# Science.net
KiCad netlist of a schematic drawn in Altium Designer
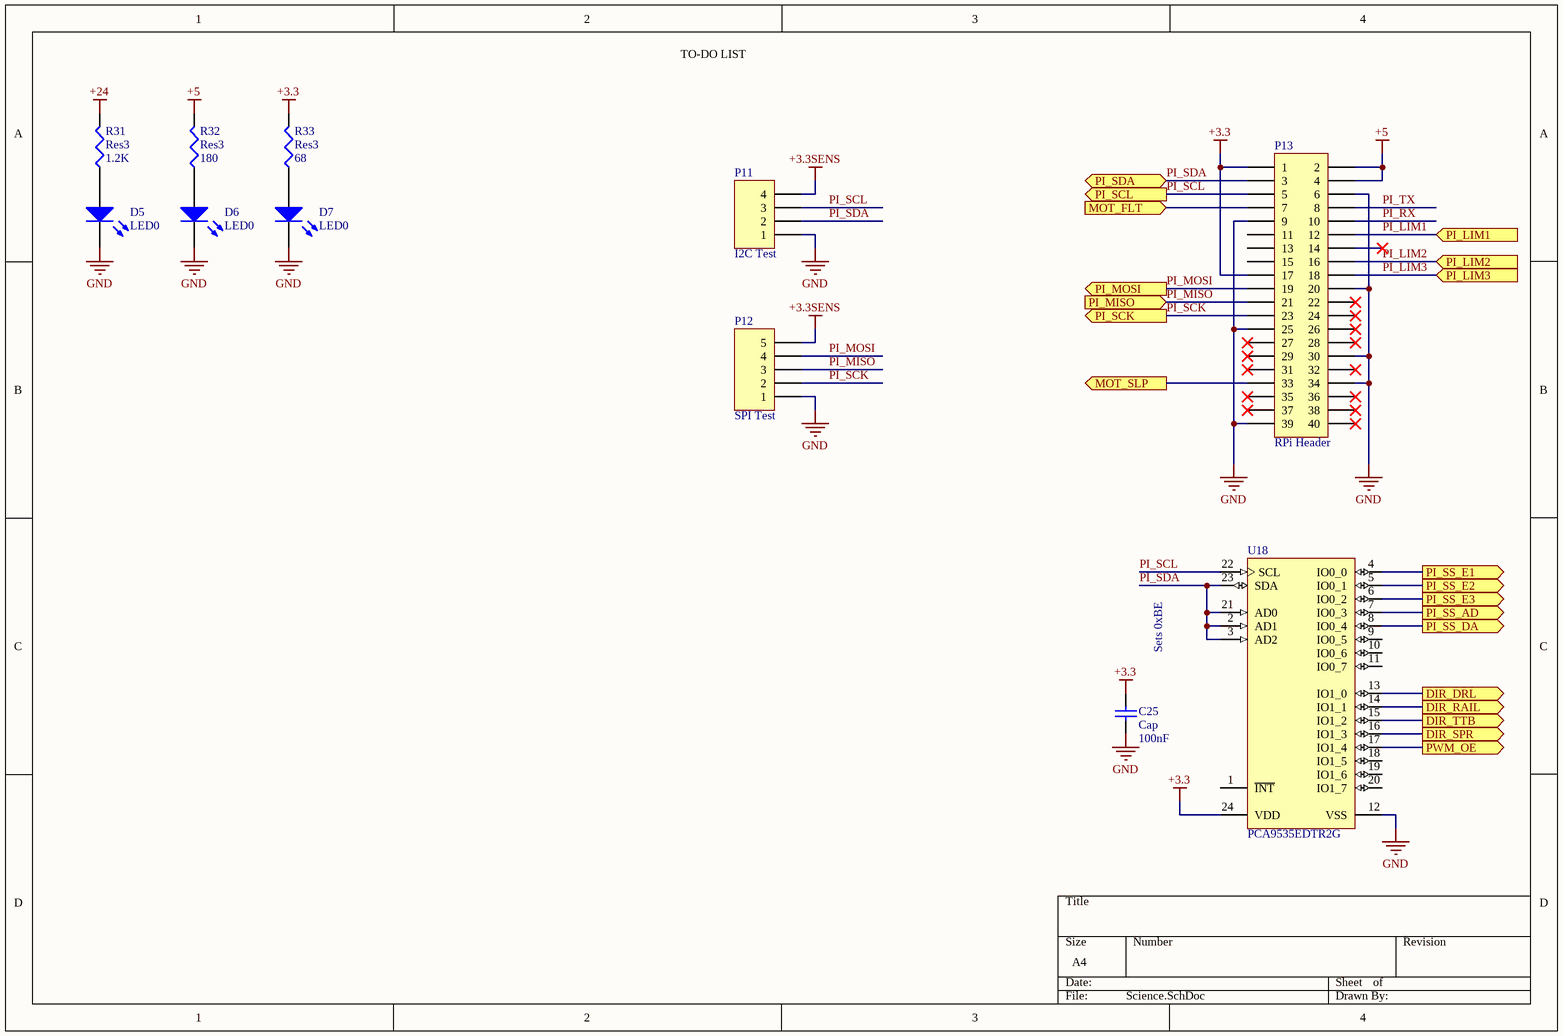
[diagram p0: Science.SchDoc]

(export (version "E")
  (design (tool "Eeschema 10.0.6"))
  (components
    (comp (ref "C25")
      (value "Cap")
      (footprint "C0805")
      (description "Capacitor")
      (fields (field (name "ALTIUM_VALUE") "100nF") (field (name "PUBLISHER") "Altium Limited"))
      (libsource (lib "Miscellaneous Devices") (part "Cap"))
    )
    (comp (ref "D5")
      (value "LED0")
      (footprint "1608[0603]")
      (description "Typical INFRARED GaAs LED")
      (fields (field (name "PUBLISHER") "Altium Limited"))
      (libsource (lib "Miscellaneous Devices") (part "LED0"))
    )
    (comp (ref "D6")
      (value "LED0")
      (footprint "1608[0603]")
      (description "Typical INFRARED GaAs LED")
      (fields (field (name "PUBLISHER") "Altium Limited"))
      (libsource (lib "Miscellaneous Devices") (part "LED0"))
    )
    (comp (ref "D7")
      (value "LED0")
      (footprint "1608[0603]")
      (description "Typical INFRARED GaAs LED")
      (fields (field (name "PUBLISHER") "Altium Limited"))
      (libsource (lib "Miscellaneous Devices") (part "LED0"))
    )
    (comp (ref "P11")
      (value "I2C Test")
      (footprint "HDR1X4")
      (description "Header, 4-Pin")
      (fields (field (name "PUBLISHER") "Altium Limited"))
      (libsource (lib "Miscellaneous Connectors") (part "Header 4"))
    )
    (comp (ref "P12")
      (value "SPI Test")
      (footprint "HDR1X5")
      (description "Header, 5-Pin")
      (fields (field (name "PUBLISHER") "Altium Limited"))
      (libsource (lib "Miscellaneous Connectors") (part "Header 5"))
    )
    (comp (ref "P13")
      (value "RPi Header")
      (footprint "RPi-3B+")
      (description "Header, 20-Pin, Dual row")
      (fields (field (name "PUBLISHER") "Altium Limited"))
      (libsource (lib "Miscellaneous Connectors") (part "Header 20X2"))
    )
    (comp (ref "R31")
      (value "Res3")
      (footprint "C0805")
      (description "Resistor")
      (fields (field (name "ALTIUM_VALUE") "1.2K") (field (name "PUBLISHER") "Altium Limited"))
      (libsource (lib "Miscellaneous Devices") (part "Res3"))
    )
    (comp (ref "R32")
      (value "Res3")
      (footprint "C0805")
      (description "Resistor")
      (fields (field (name "ALTIUM_VALUE") "180") (field (name "PUBLISHER") "Altium Limited"))
      (libsource (lib "Miscellaneous Devices") (part "Res3"))
    )
    (comp (ref "R33")
      (value "Res3")
      (footprint "C0805")
      (description "Resistor")
      (fields (field (name "ALTIUM_VALUE") "68") (field (name "PUBLISHER") "Altium Limited"))
      (libsource (lib "Miscellaneous Devices") (part "Res3"))
    )
    (comp (ref "U18")
      (value "PCA9535EDTR2G")
      (footprint "ONSC-TSSOP-24-948H_V")
      (fields (field (name "MANUFACTURER") "On Semiconductor"))
      (libsource (lib "Altium Content Vault") (part "ONSC-PCA9535E-24"))
    )
  )
  (nets
    (net (code "1") (name "+3.3") (class "Default")
      (node (ref "C25") (pin "2") (pinfunction "2_2") (pintype "passive"))
      (node (ref "P13") (pin "1") (pinfunction "1_1") (pintype "passive"))
      (node (ref "P13") (pin "17") (pinfunction "17_17") (pintype "passive"))
      (node (ref "R33") (pin "2") (pinfunction "2_2") (pintype "passive"))
      (node (ref "U18") (pin "24") (pinfunction "VDD_24") (pintype "power_in"))
    )
    (net (code "2") (name "+3.3SENS") (class "Default")
      (node (ref "P11") (pin "4") (pinfunction "4_4") (pintype "passive"))
      (node (ref "P12") (pin "5") (pinfunction "5_5") (pintype "passive"))
    )
    (net (code "3") (name "+5") (class "Default")
      (node (ref "P13") (pin "2") (pinfunction "2_2") (pintype "passive"))
      (node (ref "P13") (pin "4") (pinfunction "4_4") (pintype "passive"))
      (node (ref "R32") (pin "2") (pinfunction "2_2") (pintype "passive"))
    )
    (net (code "4") (name "+24") (class "Default")
      (node (ref "R31") (pin "2") (pinfunction "2_2") (pintype "passive"))
    )
    (net (code "5") (name "/DIR_DRL") (class "Default")
      (node (ref "U18") (pin "13") (pinfunction "IO1_0_13") (pintype "bidirectional"))
    )
    (net (code "6") (name "/DIR_RAIL") (class "Default")
      (node (ref "U18") (pin "14") (pinfunction "IO1_1_14") (pintype "bidirectional"))
    )
    (net (code "7") (name "/DIR_SPR") (class "Default")
      (node (ref "U18") (pin "16") (pinfunction "IO1_3_16") (pintype "bidirectional"))
    )
    (net (code "8") (name "/DIR_TTB") (class "Default")
      (node (ref "U18") (pin "15") (pinfunction "IO1_2_15") (pintype "bidirectional"))
    )
    (net (code "9") (name "/MOT_FLT") (class "Default")
      (node (ref "P13") (pin "7") (pinfunction "7_7") (pintype "passive"))
    )
    (net (code "10") (name "/MOT_SLP") (class "Default")
      (node (ref "P13") (pin "33") (pinfunction "33_33") (pintype "passive"))
    )
    (net (code "11") (name "/PI_LIM1") (class "Default")
      (node (ref "P13") (pin "12") (pinfunction "12_12") (pintype "passive"))
    )
    (net (code "12") (name "/PI_LIM2") (class "Default")
      (node (ref "P13") (pin "16") (pinfunction "16_16") (pintype "passive"))
    )
    (net (code "13") (name "/PI_LIM3") (class "Default")
      (node (ref "P13") (pin "18") (pinfunction "18_18") (pintype "passive"))
    )
    (net (code "14") (name "/PI_MISO") (class "Default")
      (node (ref "P12") (pin "3") (pinfunction "3_3") (pintype "passive"))
      (node (ref "P13") (pin "21") (pinfunction "21_21") (pintype "passive"))
    )
    (net (code "15") (name "/PI_MOSI") (class "Default")
      (node (ref "P12") (pin "4") (pinfunction "4_4") (pintype "passive"))
      (node (ref "P13") (pin "19") (pinfunction "19_19") (pintype "passive"))
    )
    (net (code "16") (name "/PI_RX") (class "Default")
      (node (ref "P13") (pin "10") (pinfunction "10_10") (pintype "passive"))
    )
    (net (code "17") (name "/PI_SCK") (class "Default")
      (node (ref "P12") (pin "2") (pinfunction "2_2") (pintype "passive"))
      (node (ref "P13") (pin "23") (pinfunction "23_23") (pintype "passive"))
    )
    (net (code "18") (name "/PI_SCL") (class "Default")
      (node (ref "P11") (pin "3") (pinfunction "3_3") (pintype "passive"))
      (node (ref "P13") (pin "5") (pinfunction "5_5") (pintype "passive"))
      (node (ref "U18") (pin "22") (pinfunction "SCL_22") (pintype "input"))
    )
    (net (code "19") (name "/PI_SDA") (class "Default")
      (node (ref "P11") (pin "2") (pinfunction "2_2") (pintype "passive"))
      (node (ref "P13") (pin "3") (pinfunction "3_3") (pintype "passive"))
      (node (ref "U18") (pin "2") (pinfunction "AD1_2") (pintype "input"))
      (node (ref "U18") (pin "21") (pinfunction "AD0_21") (pintype "input"))
      (node (ref "U18") (pin "23") (pinfunction "SDA_23") (pintype "bidirectional"))
      (node (ref "U18") (pin "3") (pinfunction "AD2_3") (pintype "input"))
    )
    (net (code "20") (name "/PI_SS_AD") (class "Default")
      (node (ref "U18") (pin "7") (pinfunction "IO0_3_7") (pintype "bidirectional"))
    )
    (net (code "21") (name "/PI_SS_DA") (class "Default")
      (node (ref "U18") (pin "8") (pinfunction "IO0_4_8") (pintype "bidirectional"))
    )
    (net (code "22") (name "/PI_SS_E1") (class "Default")
      (node (ref "U18") (pin "4") (pinfunction "IO0_0_4") (pintype "bidirectional"))
    )
    (net (code "23") (name "/PI_SS_E2") (class "Default")
      (node (ref "U18") (pin "5") (pinfunction "IO0_1_5") (pintype "bidirectional"))
    )
    (net (code "24") (name "/PI_SS_E3") (class "Default")
      (node (ref "U18") (pin "6") (pinfunction "IO0_2_6") (pintype "bidirectional"))
    )
    (net (code "25") (name "/PI_TX") (class "Default")
      (node (ref "P13") (pin "8") (pinfunction "8_8") (pintype "passive"))
    )
    (net (code "26") (name "/PWM_OE") (class "Default")
      (node (ref "U18") (pin "17") (pinfunction "IO1_4_17") (pintype "bidirectional"))
    )
    (net (code "27") (name "GND") (class "Default")
      (node (ref "C25") (pin "1") (pinfunction "1_1") (pintype "passive"))
      (node (ref "D5") (pin "2") (pinfunction "K_2") (pintype "passive"))
      (node (ref "D6") (pin "2") (pinfunction "K_2") (pintype "passive"))
      (node (ref "D7") (pin "2") (pinfunction "K_2") (pintype "passive"))
      (node (ref "P11") (pin "1") (pinfunction "1_1") (pintype "passive"))
      (node (ref "P12") (pin "1") (pinfunction "1_1") (pintype "passive"))
      (node (ref "P13") (pin "20") (pinfunction "20_20") (pintype "passive"))
      (node (ref "P13") (pin "25") (pinfunction "25_25") (pintype "passive"))
      (node (ref "P13") (pin "30") (pinfunction "30_30") (pintype "passive"))
      (node (ref "P13") (pin "34") (pinfunction "34_34") (pintype "passive"))
      (node (ref "P13") (pin "39") (pinfunction "39_39") (pintype "passive"))
      (node (ref "P13") (pin "6") (pinfunction "6_6") (pintype "passive"))
      (node (ref "P13") (pin "9") (pinfunction "9_9") (pintype "passive"))
      (node (ref "U18") (pin "12") (pinfunction "VSS_12") (pintype "power_in"))
    )
    (net (code "28") (name "Net-(D5-A)") (class "Default")
      (node (ref "D5") (pin "1") (pinfunction "A_1") (pintype "passive"))
      (node (ref "R31") (pin "1") (pinfunction "1_1") (pintype "passive"))
    )
    (net (code "29") (name "Net-(D6-A)") (class "Default")
      (node (ref "D6") (pin "1") (pinfunction "A_1") (pintype "passive"))
      (node (ref "R32") (pin "1") (pinfunction "1_1") (pintype "passive"))
    )
    (net (code "30") (name "Net-(D7-A)") (class "Default")
      (node (ref "D7") (pin "1") (pinfunction "A_1") (pintype "passive"))
      (node (ref "R33") (pin "1") (pinfunction "1_1") (pintype "passive"))
    )
    (net (code "31") (name "unconnected-(P13-Pad11)") (class "Default")
      (node (ref "P13") (pin "11") (pinfunction "11_11") (pintype "passive"))
    )
    (net (code "32") (name "unconnected-(P13-Pad13)") (class "Default")
      (node (ref "P13") (pin "13") (pinfunction "13_13") (pintype "passive"))
    )
    (net (code "33") (name "unconnected-(P13-Pad14)") (class "Default")
      (node (ref "P13") (pin "14") (pinfunction "14_14") (pintype "passive+no_connect"))
    )
    (net (code "34") (name "unconnected-(P13-Pad15)") (class "Default")
      (node (ref "P13") (pin "15") (pinfunction "15_15") (pintype "passive"))
    )
    (net (code "35") (name "unconnected-(P13-Pad22)") (class "Default")
      (node (ref "P13") (pin "22") (pinfunction "22_22") (pintype "passive+no_connect"))
    )
    (net (code "36") (name "unconnected-(P13-Pad24)") (class "Default")
      (node (ref "P13") (pin "24") (pinfunction "24_24") (pintype "passive+no_connect"))
    )
    (net (code "37") (name "unconnected-(P13-Pad26)") (class "Default")
      (node (ref "P13") (pin "26") (pinfunction "26_26") (pintype "passive+no_connect"))
    )
    (net (code "38") (name "unconnected-(P13-Pad27)") (class "Default")
      (node (ref "P13") (pin "27") (pinfunction "27_27") (pintype "passive+no_connect"))
    )
    (net (code "39") (name "unconnected-(P13-Pad28)") (class "Default")
      (node (ref "P13") (pin "28") (pinfunction "28_28") (pintype "passive+no_connect"))
    )
    (net (code "40") (name "unconnected-(P13-Pad29)") (class "Default")
      (node (ref "P13") (pin "29") (pinfunction "29_29") (pintype "passive+no_connect"))
    )
    (net (code "41") (name "unconnected-(P13-Pad31)") (class "Default")
      (node (ref "P13") (pin "31") (pinfunction "31_31") (pintype "passive+no_connect"))
    )
    (net (code "42") (name "unconnected-(P13-Pad32)") (class "Default")
      (node (ref "P13") (pin "32") (pinfunction "32_32") (pintype "passive+no_connect"))
    )
    (net (code "43") (name "unconnected-(P13-Pad35)") (class "Default")
      (node (ref "P13") (pin "35") (pinfunction "35_35") (pintype "passive+no_connect"))
    )
    (net (code "44") (name "unconnected-(P13-Pad36)") (class "Default")
      (node (ref "P13") (pin "36") (pinfunction "36_36") (pintype "passive+no_connect"))
    )
    (net (code "45") (name "unconnected-(P13-Pad37)") (class "Default")
      (node (ref "P13") (pin "37") (pinfunction "37_37") (pintype "passive+no_connect"))
    )
    (net (code "46") (name "unconnected-(P13-Pad38)") (class "Default")
      (node (ref "P13") (pin "38") (pinfunction "38_38") (pintype "passive+no_connect"))
    )
    (net (code "47") (name "unconnected-(P13-Pad40)") (class "Default")
      (node (ref "P13") (pin "40") (pinfunction "40_40") (pintype "passive+no_connect"))
    )
    (net (code "48") (name "unconnected-(U18-IO0_5-Pad9)") (class "Default")
      (node (ref "U18") (pin "9") (pinfunction "IO0_5_9") (pintype "bidirectional"))
    )
    (net (code "49") (name "unconnected-(U18-IO0_6-Pad10)") (class "Default")
      (node (ref "U18") (pin "10") (pinfunction "IO0_6_10") (pintype "bidirectional"))
    )
    (net (code "50") (name "unconnected-(U18-IO0_7-Pad11)") (class "Default")
      (node (ref "U18") (pin "11") (pinfunction "IO0_7_11") (pintype "bidirectional"))
    )
    (net (code "51") (name "unconnected-(U18-IO1_5-Pad18)") (class "Default")
      (node (ref "U18") (pin "18") (pinfunction "IO1_5_18") (pintype "bidirectional"))
    )
    (net (code "52") (name "unconnected-(U18-IO1_6-Pad19)") (class "Default")
      (node (ref "U18") (pin "19") (pinfunction "IO1_6_19") (pintype "bidirectional"))
    )
    (net (code "53") (name "unconnected-(U18-IO1_7-Pad20)") (class "Default")
      (node (ref "U18") (pin "20") (pinfunction "IO1_7_20") (pintype "bidirectional"))
    )
    (net (code "54") (name "unconnected-(U18-~{INT}-Pad1)") (class "Default")
      (node (ref "U18") (pin "1") (pinfunction "~{INT}_1") (pintype "open_collector"))
    )
  )
)
